# 2_mb_conn.net
KiCad netlist of a schematic drawn in Altium Designer
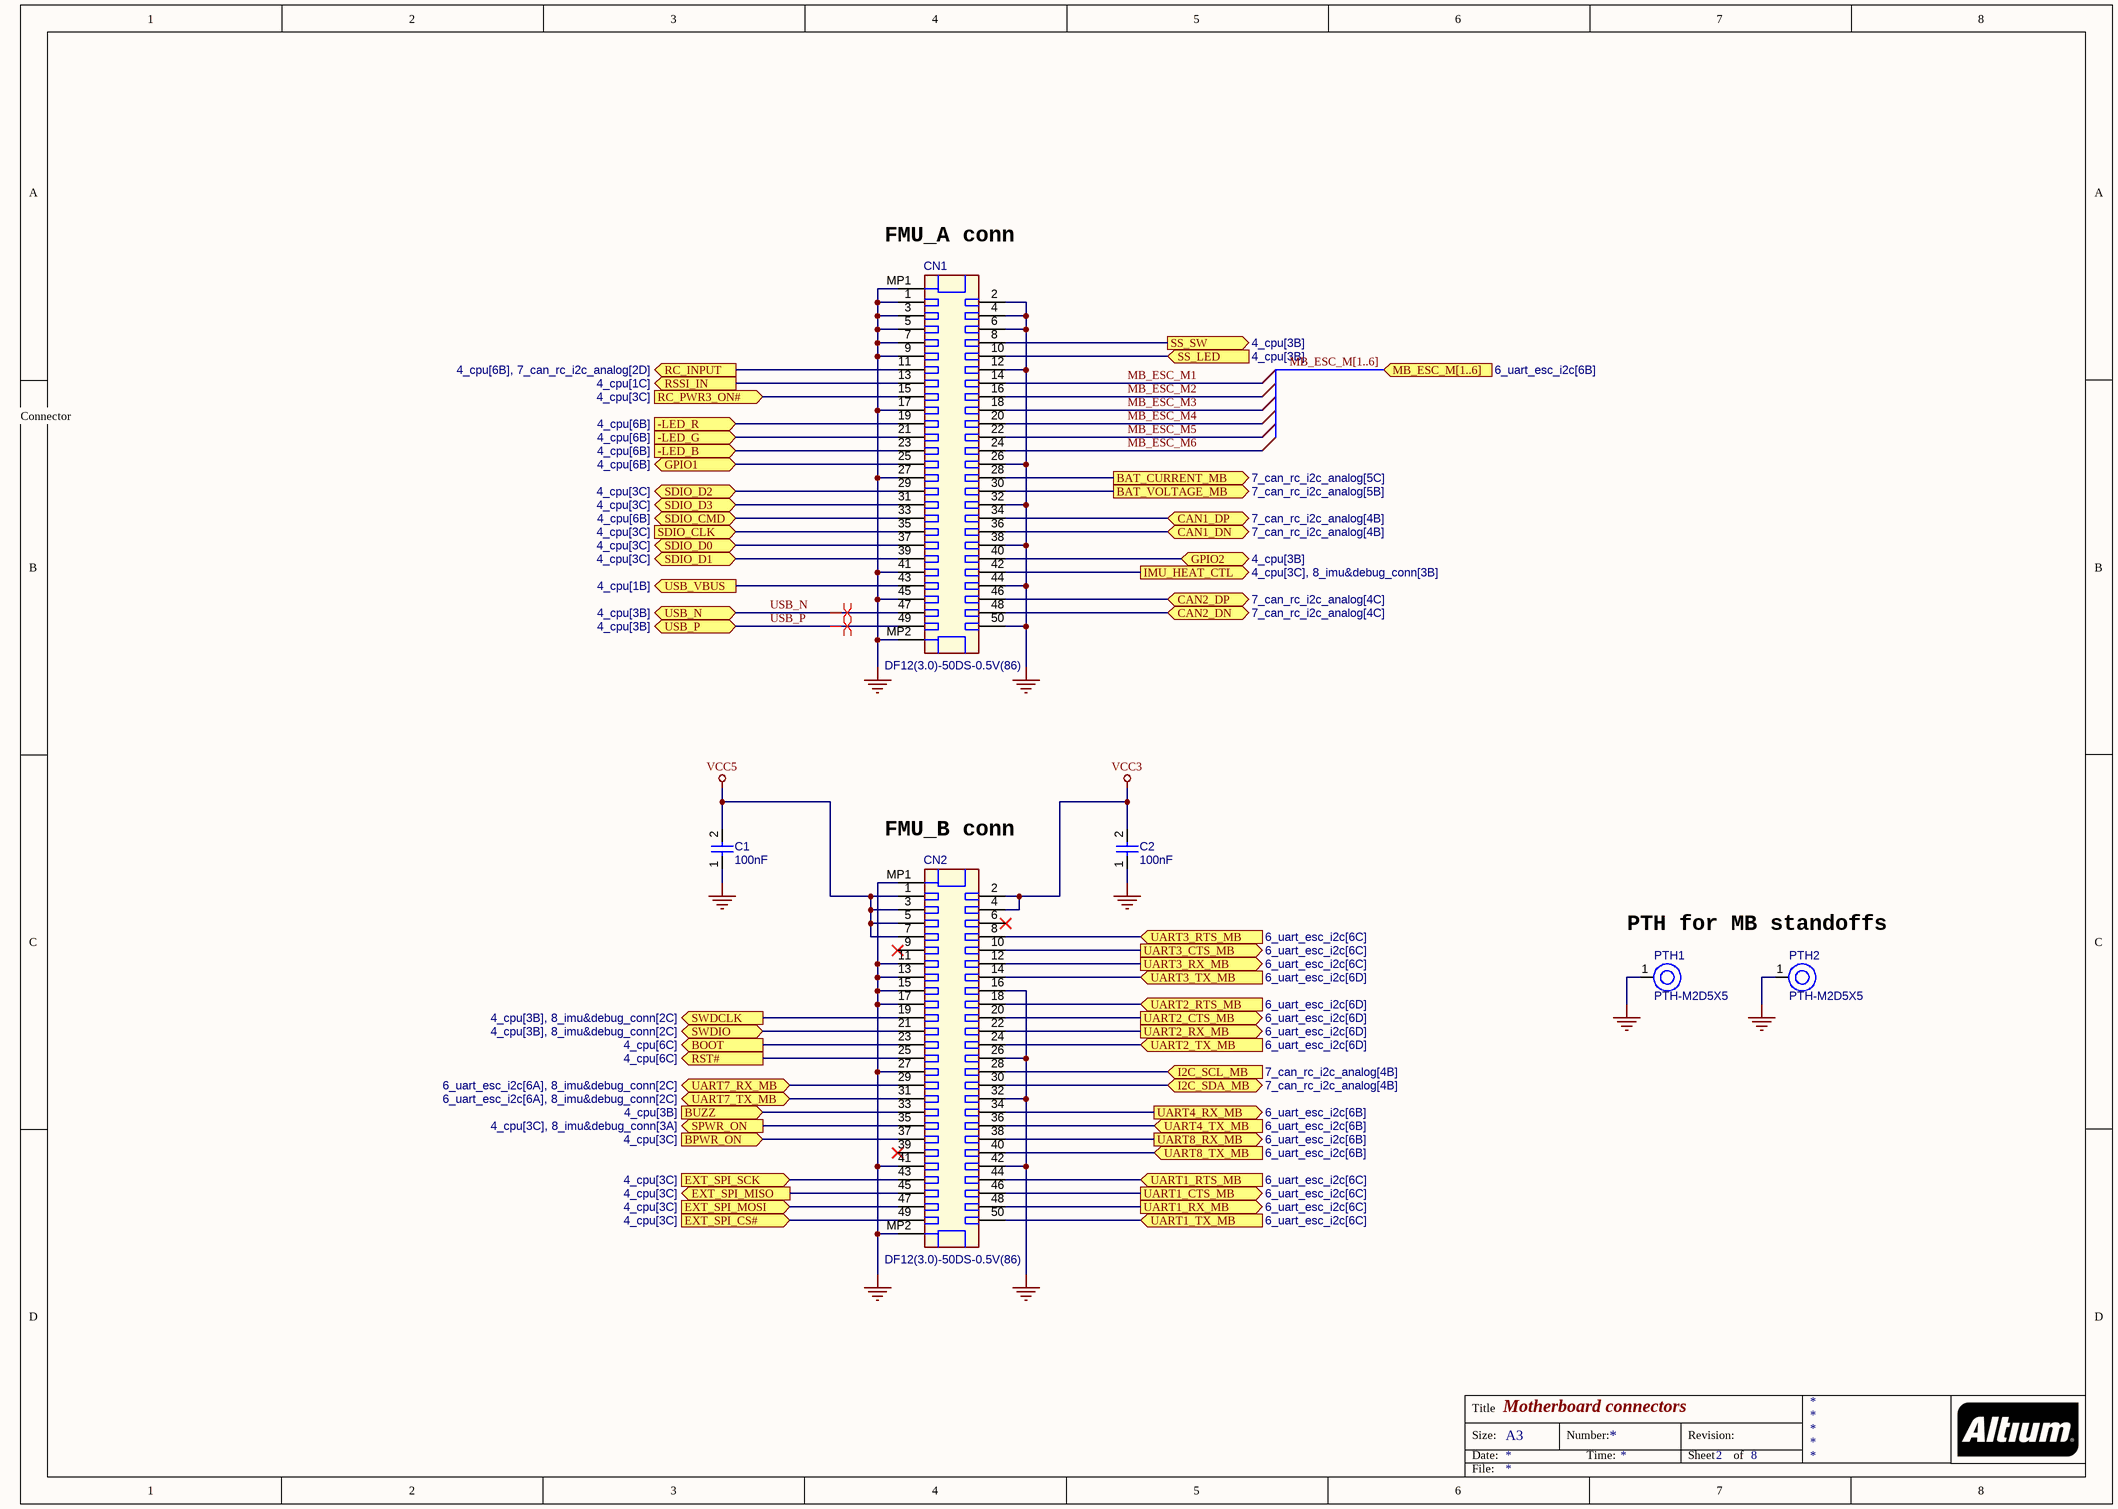
[diagram p0: 2_mb_conn.SchDoc]

(export (version "E")
  (design (tool "Eeschema 10.0.6"))
  (components
    (comp (ref "C1")
      (value "100nF")
      (footprint "CAPC0402(1005)60_L")
      (description "Chip Capacitor, 100nF +/-20%, 10V, 0402, Thickness 0.6 mm")
      (fields (field (name "TOLERANCE") "20%") (field (name "MANUFACTURER") "KEMET"))
      (libsource (lib "Kame_FMU") (part "Capacitor 100nF +/-20% 10V 0402"))
    )
    (comp (ref "C2")
      (value "100nF")
      (footprint "CAPC0402(1005)60_L")
      (description "Chip Capacitor, 100nF +/-20%, 10V, 0402, Thickness 0.6 mm")
      (fields (field (name "TOLERANCE") "20%") (field (name "MANUFACTURER") "KEMET"))
      (libsource (lib "Kame_FMU") (part "Capacitor 100nF +/-20% 10V 0402"))
    )
    (comp (ref "CN1")
      (value "DF12(3.0)-50DS-0.5V(86)")
      (footprint "HIRO-DF12(3.0)-50DS-0.5V_V")
      (description "Receptacle Connector, 50 V, 0.3 A, -45 to 125 degC, RoHS, Tape and Reel")
      (fields (field (name "MANUFACTURER") "Hirose"))
      (libsource (lib "Kame_FMU") (part "DF12(3.0)-50DS-0.5V(86)"))
    )
    (comp (ref "CN2")
      (value "DF12(3.0)-50DS-0.5V(86)")
      (footprint "HIRO-DF12(3.0)-50DS-0.5V_V")
      (description "Receptacle Connector, 50 V, 0.3 A, -45 to 125 degC, RoHS, Tape and Reel")
      (fields (field (name "MANUFACTURER") "Hirose"))
      (libsource (lib "Kame_FMU") (part "DF12(3.0)-50DS-0.5V(86)"))
    )
    (comp (ref "PTH1")
      (value "PTH-M2D5X5")
      (footprint "PTH-M2D5X5")
      (description "M2 PTH (2.5mm), 5mm pad")
      (libsource (lib "Kame_FMU") (part "PTH-M2D5X5"))
    )
    (comp (ref "PTH2")
      (value "PTH-M2D5X5")
      (footprint "PTH-M2D5X5")
      (description "M2 PTH (2.5mm), 5mm pad")
      (libsource (lib "Kame_FMU") (part "PTH-M2D5X5"))
    )
  )
  (nets
    (net (code "1") (name "/-LED_B") (class "Default")
      (node (ref "CN1") (pin "23") (pinfunction "23_23") (pintype "passive"))
    )
    (net (code "2") (name "/-LED_G") (class "Default")
      (node (ref "CN1") (pin "21") (pinfunction "21_21") (pintype "passive"))
    )
    (net (code "3") (name "/-LED_R") (class "Default")
      (node (ref "CN1") (pin "19") (pinfunction "19_19") (pintype "passive"))
    )
    (net (code "4") (name "/BAT_CURRENT_MB") (class "Default")
      (node (ref "CN1") (pin "28") (pinfunction "28_28") (pintype "passive"))
    )
    (net (code "5") (name "/BAT_VOLTAGE_MB") (class "Default")
      (node (ref "CN1") (pin "30") (pinfunction "30_30") (pintype "passive"))
    )
    (net (code "6") (name "/BOOT") (class "Default")
      (node (ref "CN2") (pin "23") (pinfunction "23_23") (pintype "passive"))
    )
    (net (code "7") (name "/BPWR_ON") (class "Default")
      (node (ref "CN2") (pin "37") (pinfunction "37_37") (pintype "passive"))
    )
    (net (code "8") (name "/BUZZ") (class "Default")
      (node (ref "CN2") (pin "33") (pinfunction "33_33") (pintype "passive"))
    )
    (net (code "9") (name "/CAN1_DN") (class "Default")
      (node (ref "CN1") (pin "36") (pinfunction "36_36") (pintype "passive"))
    )
    (net (code "10") (name "/CAN1_DP") (class "Default")
      (node (ref "CN1") (pin "34") (pinfunction "34_34") (pintype "passive"))
    )
    (net (code "11") (name "/CAN2_DN") (class "Default")
      (node (ref "CN1") (pin "48") (pinfunction "48_48") (pintype "passive"))
    )
    (net (code "12") (name "/CAN2_DP") (class "Default")
      (node (ref "CN1") (pin "46") (pinfunction "46_46") (pintype "passive"))
    )
    (net (code "13") (name "/EXT_SPI_CS#") (class "Default")
      (node (ref "CN2") (pin "49") (pinfunction "49_49") (pintype "passive"))
    )
    (net (code "14") (name "/EXT_SPI_MISO") (class "Default")
      (node (ref "CN2") (pin "45") (pinfunction "45_45") (pintype "passive"))
    )
    (net (code "15") (name "/EXT_SPI_MOSI") (class "Default")
      (node (ref "CN2") (pin "47") (pinfunction "47_47") (pintype "passive"))
    )
    (net (code "16") (name "/EXT_SPI_SCK") (class "Default")
      (node (ref "CN2") (pin "43") (pinfunction "43_43") (pintype "passive"))
    )
    (net (code "17") (name "/GPIO1") (class "Default")
      (node (ref "CN1") (pin "25") (pinfunction "25_25") (pintype "passive"))
    )
    (net (code "18") (name "/GPIO2") (class "Default")
      (node (ref "CN1") (pin "40") (pinfunction "40_40") (pintype "passive"))
    )
    (net (code "19") (name "/I2C_SCL_MB") (class "Default")
      (node (ref "CN2") (pin "28") (pinfunction "28_28") (pintype "passive"))
    )
    (net (code "20") (name "/I2C_SDA_MB") (class "Default")
      (node (ref "CN2") (pin "30") (pinfunction "30_30") (pintype "passive"))
    )
    (net (code "21") (name "/IMU_HEAT_CTL") (class "Default")
      (node (ref "CN1") (pin "42") (pinfunction "42_42") (pintype "passive"))
    )
    (net (code "22") (name "/MB_ESC_M1") (class "Default")
      (node (ref "CN1") (pin "14") (pinfunction "14_14") (pintype "passive"))
    )
    (net (code "23") (name "/MB_ESC_M2") (class "Default")
      (node (ref "CN1") (pin "16") (pinfunction "16_16") (pintype "passive"))
    )
    (net (code "24") (name "/MB_ESC_M3") (class "Default")
      (node (ref "CN1") (pin "18") (pinfunction "18_18") (pintype "passive"))
    )
    (net (code "25") (name "/MB_ESC_M4") (class "Default")
      (node (ref "CN1") (pin "20") (pinfunction "20_20") (pintype "passive"))
    )
    (net (code "26") (name "/MB_ESC_M5") (class "Default")
      (node (ref "CN1") (pin "22") (pinfunction "22_22") (pintype "passive"))
    )
    (net (code "27") (name "/MB_ESC_M6") (class "Default")
      (node (ref "CN1") (pin "24") (pinfunction "24_24") (pintype "passive"))
    )
    (net (code "29") (name "/RC_INPUT") (class "Default")
      (node (ref "CN1") (pin "11") (pinfunction "11_11") (pintype "passive"))
    )
    (net (code "30") (name "/RC_PWR3_ON#") (class "Default")
      (node (ref "CN1") (pin "15") (pinfunction "15_15") (pintype "passive"))
    )
    (net (code "31") (name "/RSSI_IN") (class "Default")
      (node (ref "CN1") (pin "13") (pinfunction "13_13") (pintype "passive"))
    )
    (net (code "32") (name "/RST#") (class "Default")
      (node (ref "CN2") (pin "25") (pinfunction "25_25") (pintype "passive"))
    )
    (net (code "33") (name "/SDIO_CLK") (class "Default")
      (node (ref "CN1") (pin "35") (pinfunction "35_35") (pintype "passive"))
    )
    (net (code "34") (name "/SDIO_CMD") (class "Default")
      (node (ref "CN1") (pin "33") (pinfunction "33_33") (pintype "passive"))
    )
    (net (code "35") (name "/SDIO_D0") (class "Default")
      (node (ref "CN1") (pin "37") (pinfunction "37_37") (pintype "passive"))
    )
    (net (code "36") (name "/SDIO_D1") (class "Default")
      (node (ref "CN1") (pin "39") (pinfunction "39_39") (pintype "passive"))
    )
    (net (code "37") (name "/SDIO_D2") (class "Default")
      (node (ref "CN1") (pin "29") (pinfunction "29_29") (pintype "passive"))
    )
    (net (code "38") (name "/SDIO_D3") (class "Default")
      (node (ref "CN1") (pin "31") (pinfunction "31_31") (pintype "passive"))
    )
    (net (code "39") (name "/SPWR_ON") (class "Default")
      (node (ref "CN2") (pin "35") (pinfunction "35_35") (pintype "passive"))
    )
    (net (code "40") (name "/SS_LED") (class "Default")
      (node (ref "CN1") (pin "10") (pinfunction "10_10") (pintype "passive"))
    )
    (net (code "41") (name "/SS_SW") (class "Default")
      (node (ref "CN1") (pin "8") (pinfunction "8_8") (pintype "passive"))
    )
    (net (code "42") (name "/SWDCLK") (class "Default")
      (node (ref "CN2") (pin "19") (pinfunction "19_19") (pintype "passive"))
    )
    (net (code "43") (name "/SWDIO") (class "Default")
      (node (ref "CN2") (pin "21") (pinfunction "21_21") (pintype "passive"))
    )
    (net (code "44") (name "/UART1_CTS_MB") (class "Default")
      (node (ref "CN2") (pin "46") (pinfunction "46_46") (pintype "passive"))
    )
    (net (code "45") (name "/UART1_RTS_MB") (class "Default")
      (node (ref "CN2") (pin "44") (pinfunction "44_44") (pintype "passive"))
    )
    (net (code "46") (name "/UART1_RX_MB") (class "Default")
      (node (ref "CN2") (pin "48") (pinfunction "48_48") (pintype "passive"))
    )
    (net (code "47") (name "/UART1_TX_MB") (class "Default")
      (node (ref "CN2") (pin "50") (pinfunction "50_50") (pintype "passive"))
    )
    (net (code "48") (name "/UART2_CTS_MB") (class "Default")
      (node (ref "CN2") (pin "20") (pinfunction "20_20") (pintype "passive"))
    )
    (net (code "49") (name "/UART2_RTS_MB") (class "Default")
      (node (ref "CN2") (pin "18") (pinfunction "18_18") (pintype "passive"))
    )
    (net (code "50") (name "/UART2_RX_MB") (class "Default")
      (node (ref "CN2") (pin "22") (pinfunction "22_22") (pintype "passive"))
    )
    (net (code "51") (name "/UART2_TX_MB") (class "Default")
      (node (ref "CN2") (pin "24") (pinfunction "24_24") (pintype "passive"))
    )
    (net (code "52") (name "/UART3_CTS_MB") (class "Default")
      (node (ref "CN2") (pin "10") (pinfunction "10_10") (pintype "passive"))
    )
    (net (code "53") (name "/UART3_RTS_MB") (class "Default")
      (node (ref "CN2") (pin "8") (pinfunction "8_8") (pintype "passive"))
    )
    (net (code "54") (name "/UART3_RX_MB") (class "Default")
      (node (ref "CN2") (pin "12") (pinfunction "12_12") (pintype "passive"))
    )
    (net (code "55") (name "/UART3_TX_MB") (class "Default")
      (node (ref "CN2") (pin "14") (pinfunction "14_14") (pintype "passive"))
    )
    (net (code "56") (name "/UART4_RX_MB") (class "Default")
      (node (ref "CN2") (pin "34") (pinfunction "34_34") (pintype "passive"))
    )
    (net (code "57") (name "/UART4_TX_MB") (class "Default")
      (node (ref "CN2") (pin "36") (pinfunction "36_36") (pintype "passive"))
    )
    (net (code "58") (name "/UART7_RX_MB") (class "Default")
      (node (ref "CN2") (pin "29") (pinfunction "29_29") (pintype "passive"))
    )
    (net (code "59") (name "/UART7_TX_MB") (class "Default")
      (node (ref "CN2") (pin "31") (pinfunction "31_31") (pintype "passive"))
    )
    (net (code "60") (name "/UART8_RX_MB") (class "Default")
      (node (ref "CN2") (pin "38") (pinfunction "38_38") (pintype "passive"))
    )
    (net (code "61") (name "/UART8_TX_MB") (class "Default")
      (node (ref "CN2") (pin "40") (pinfunction "40_40") (pintype "passive"))
    )
    (net (code "62") (name "/USB_N") (class "Default")
      (node (ref "CN1") (pin "47") (pinfunction "47_47") (pintype "passive"))
    )
    (net (code "63") (name "/USB_P") (class "Default")
      (node (ref "CN1") (pin "49") (pinfunction "49_49") (pintype "passive"))
    )
    (net (code "64") (name "/USB_VBUS") (class "Default")
      (node (ref "CN1") (pin "43") (pinfunction "43_43") (pintype "passive"))
    )
    (net (code "65") (name "GND") (class "Default")
      (node (ref "C1") (pin "1") (pinfunction "1_1") (pintype "passive"))
      (node (ref "C2") (pin "1") (pinfunction "1_1") (pintype "passive"))
      (node (ref "CN1") (pin "1") (pinfunction "1_1") (pintype "passive"))
      (node (ref "CN1") (pin "12") (pinfunction "12_12") (pintype "passive"))
      (node (ref "CN1") (pin "17") (pinfunction "17_17") (pintype "passive"))
      (node (ref "CN1") (pin "2") (pinfunction "2_2") (pintype "passive"))
      (node (ref "CN1") (pin "26") (pinfunction "26_26") (pintype "passive"))
      (node (ref "CN1") (pin "27") (pinfunction "27_27") (pintype "passive"))
      (node (ref "CN1") (pin "3") (pinfunction "3_3") (pintype "passive"))
      (node (ref "CN1") (pin "32") (pinfunction "32_32") (pintype "passive"))
      (node (ref "CN1") (pin "38") (pinfunction "38_38") (pintype "passive"))
      (node (ref "CN1") (pin "4") (pinfunction "4_4") (pintype "passive"))
      (node (ref "CN1") (pin "41") (pinfunction "41_41") (pintype "passive"))
      (node (ref "CN1") (pin "44") (pinfunction "44_44") (pintype "passive"))
      (node (ref "CN1") (pin "45") (pinfunction "45_45") (pintype "passive"))
      (node (ref "CN1") (pin "5") (pinfunction "5_5") (pintype "passive"))
      (node (ref "CN1") (pin "50") (pinfunction "50_50") (pintype "passive"))
      (node (ref "CN1") (pin "6") (pinfunction "6_6") (pintype "passive"))
      (node (ref "CN1") (pin "7") (pinfunction "7_7") (pintype "passive"))
      (node (ref "CN1") (pin "9") (pinfunction "9_9") (pintype "passive"))
      (node (ref "CN1") (pin "MP1") (pinfunction "MP1_MP1") (pintype "passive"))
      (node (ref "CN1") (pin "MP2") (pinfunction "MP2_MP2") (pintype "passive"))
      (node (ref "CN2") (pin "11") (pinfunction "11_11") (pintype "passive"))
      (node (ref "CN2") (pin "13") (pinfunction "13_13") (pintype "passive"))
      (node (ref "CN2") (pin "15") (pinfunction "15_15") (pintype "passive"))
      (node (ref "CN2") (pin "16") (pinfunction "16_16") (pintype "passive"))
      (node (ref "CN2") (pin "17") (pinfunction "17_17") (pintype "passive"))
      (node (ref "CN2") (pin "26") (pinfunction "26_26") (pintype "passive"))
      (node (ref "CN2") (pin "27") (pinfunction "27_27") (pintype "passive"))
      (node (ref "CN2") (pin "32") (pinfunction "32_32") (pintype "passive"))
      (node (ref "CN2") (pin "41") (pinfunction "41_41") (pintype "passive"))
      (node (ref "CN2") (pin "42") (pinfunction "42_42") (pintype "passive"))
      (node (ref "CN2") (pin "MP1") (pinfunction "MP1_MP1") (pintype "passive"))
      (node (ref "CN2") (pin "MP2") (pinfunction "MP2_MP2") (pintype "passive"))
      (node (ref "PTH1") (pin "1") (pinfunction "H1_1") (pintype "passive"))
      (node (ref "PTH2") (pin "1") (pinfunction "H1_1") (pintype "passive"))
    )
    (net (code "66") (name "VCC3") (class "Default")
      (node (ref "C2") (pin "2") (pinfunction "2_2") (pintype "passive"))
      (node (ref "CN2") (pin "2") (pinfunction "2_2") (pintype "passive"))
      (node (ref "CN2") (pin "4") (pinfunction "4_4") (pintype "passive"))
    )
    (net (code "67") (name "VCC5") (class "Default")
      (node (ref "C1") (pin "2") (pinfunction "2_2") (pintype "passive"))
      (node (ref "CN2") (pin "1") (pinfunction "1_1") (pintype "passive"))
      (node (ref "CN2") (pin "3") (pinfunction "3_3") (pintype "passive"))
      (node (ref "CN2") (pin "5") (pinfunction "5_5") (pintype "passive"))
      (node (ref "CN2") (pin "7") (pinfunction "7_7") (pintype "passive"))
    )
    (net (code "68") (name "unconnected-(CN2-Pad6)") (class "Default")
      (node (ref "CN2") (pin "6") (pinfunction "6_6") (pintype "passive+no_connect"))
    )
    (net (code "69") (name "unconnected-(CN2-Pad9)") (class "Default")
      (node (ref "CN2") (pin "9") (pinfunction "9_9") (pintype "passive+no_connect"))
    )
    (net (code "70") (name "unconnected-(CN2-Pad39)") (class "Default")
      (node (ref "CN2") (pin "39") (pinfunction "39_39") (pintype "passive+no_connect"))
    )
  )
)
